# 2024-4T-MNT-1.net
KiCad netlist of a schematic drawn in EasyEDA Pro
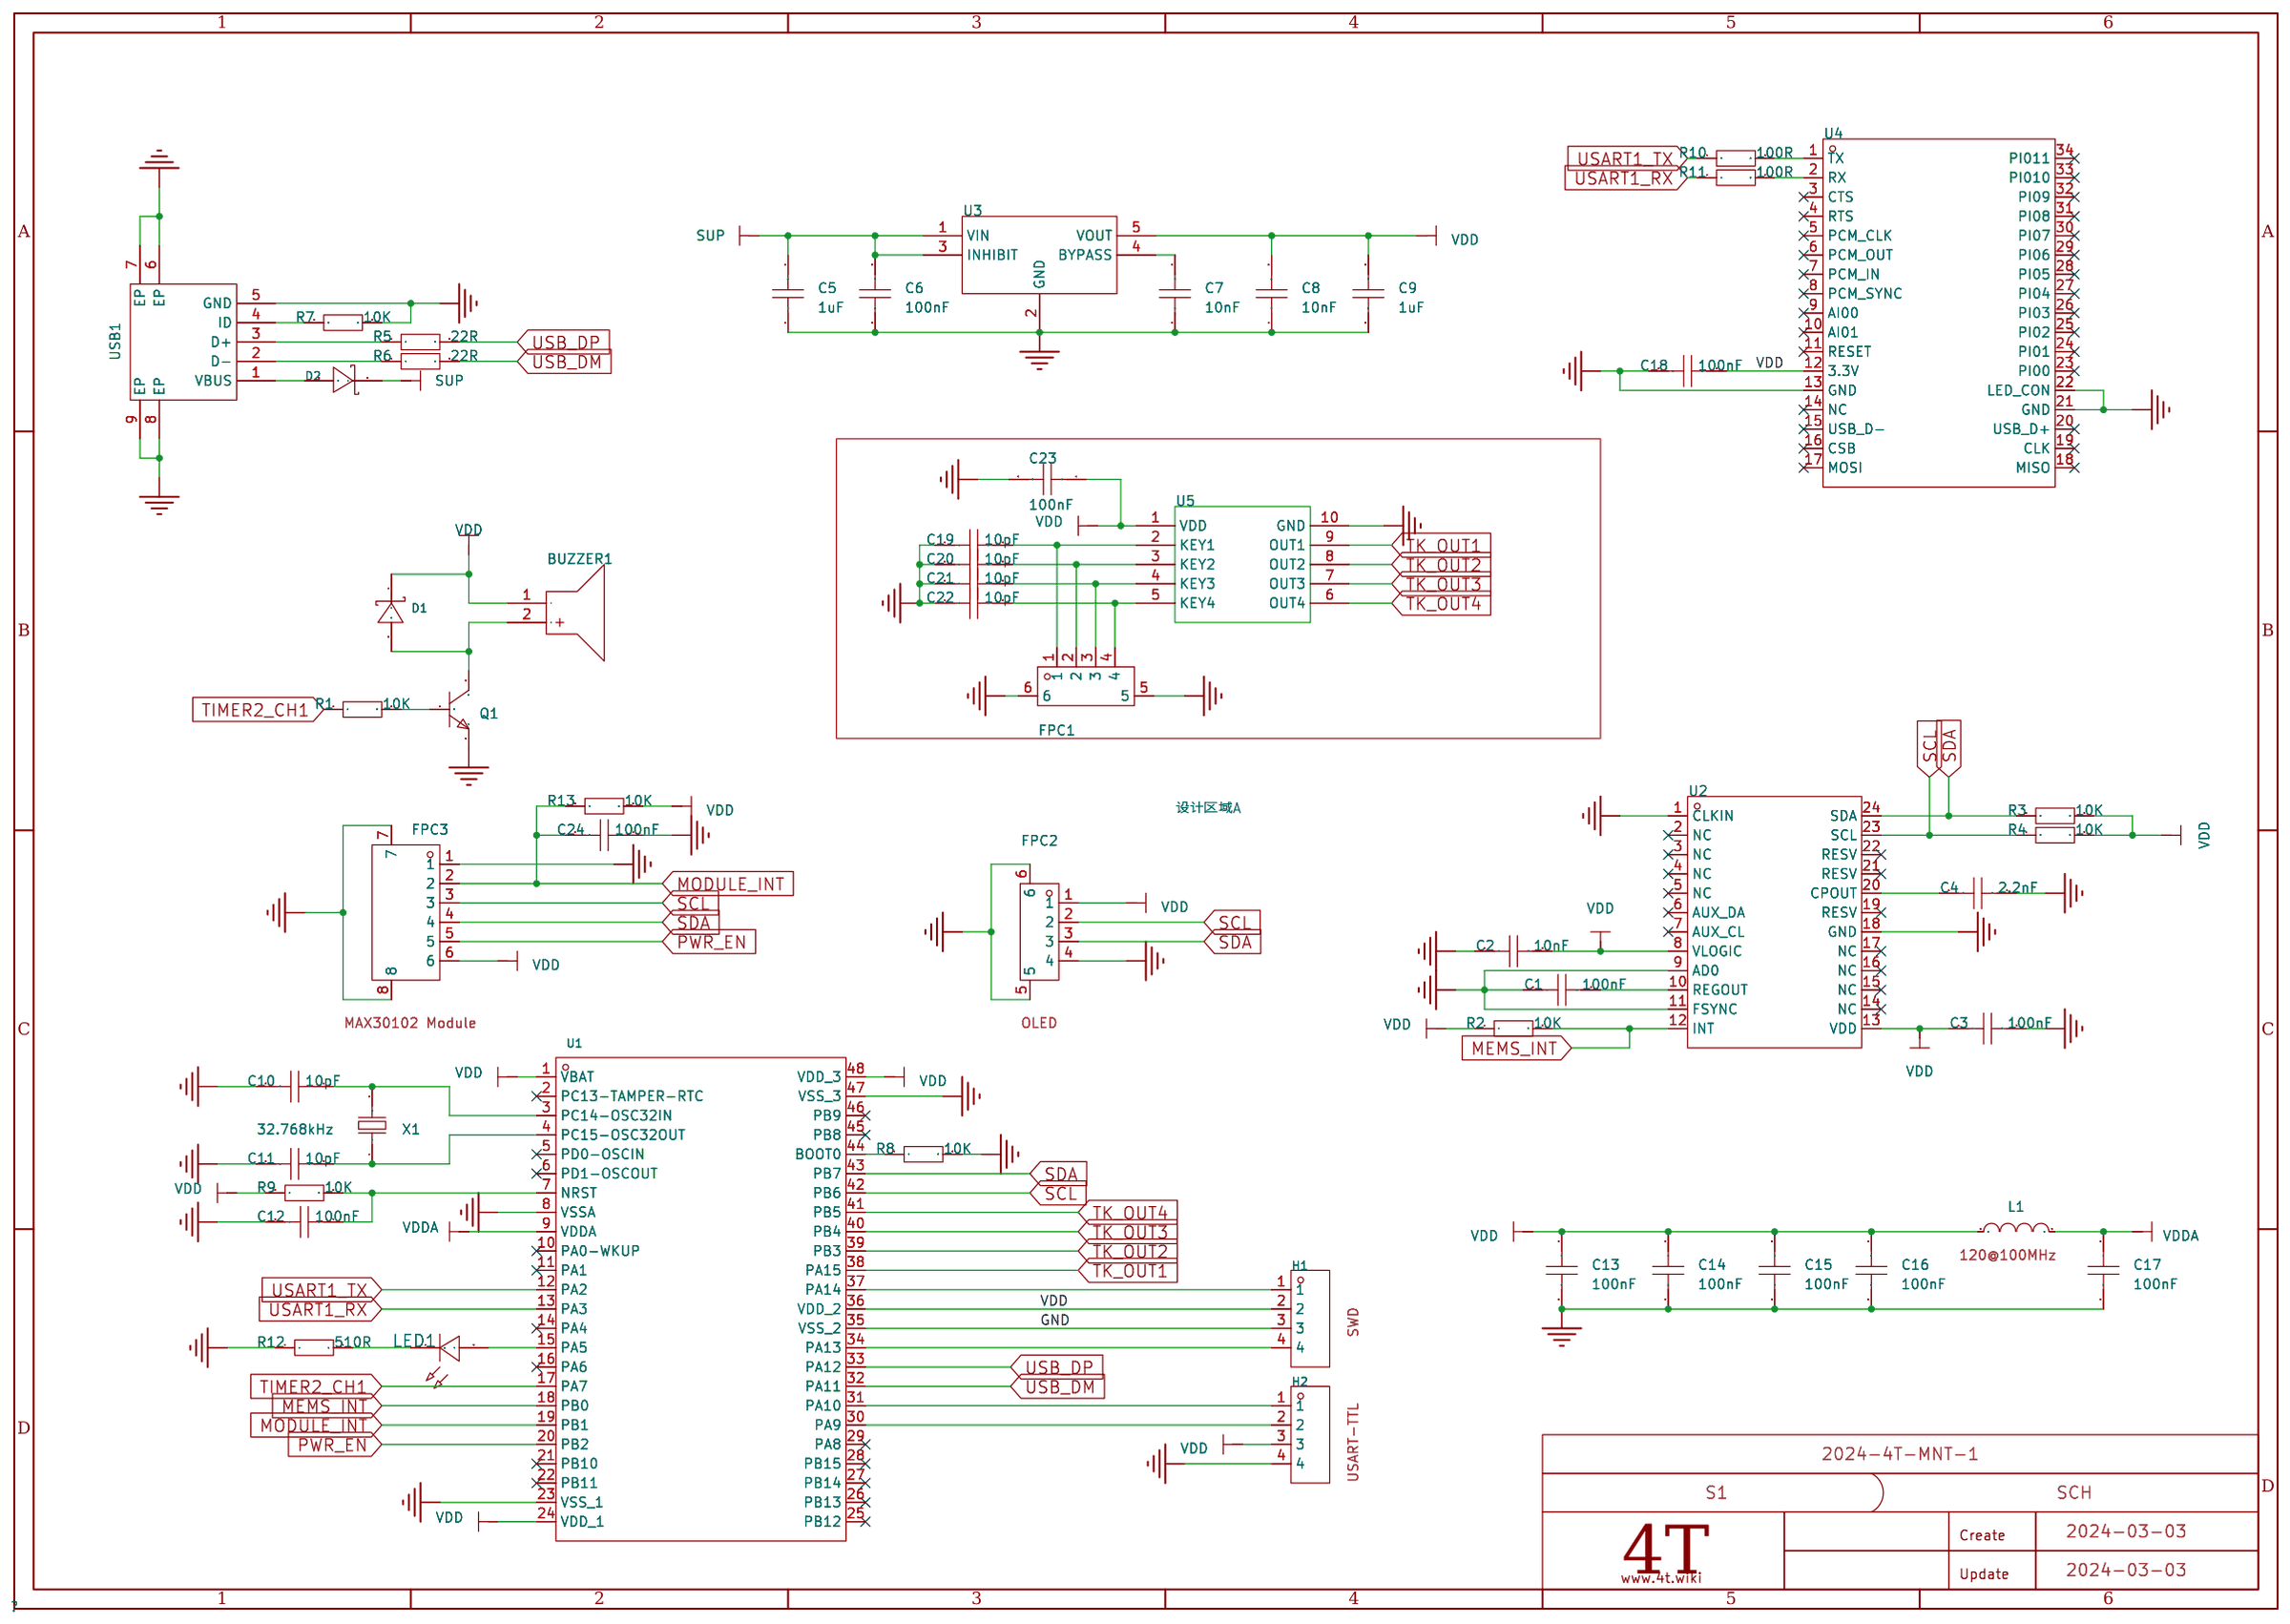
[diagram p0: schematic sheet]

(export (version "E")
  (design (tool "Eeschema 10.0.6"))
  (components
    (comp (ref "BUZZER1")
      (value "buzzer")
      (footprint "easyedapro:BUZ-TH_BD12.0-P6.00-D0.9-RD")
      (libsource (lib "easyedapro") (part "BUZZER"))
    )
    (comp (ref "C1")
      (value "100nF")
      (footprint "easyedapro:C0805")
      (libsource (lib "easyedapro") (part "CapAcitance"))
    )
    (comp (ref "C2")
      (value "10nF")
      (footprint "easyedapro:C0805")
      (libsource (lib "easyedapro") (part "CapAcitance"))
    )
    (comp (ref "C3")
      (value "100nF")
      (footprint "easyedapro:C0805")
      (libsource (lib "easyedapro") (part "CapAcitance"))
    )
    (comp (ref "C4")
      (value "2.2nF")
      (footprint "easyedapro:C0805")
      (libsource (lib "easyedapro") (part "CapAcitance"))
    )
    (comp (ref "C5")
      (value "1uF")
      (footprint "easyedapro:C0805")
      (libsource (lib "easyedapro") (part "CapAcitance"))
    )
    (comp (ref "C6")
      (value "100nF")
      (footprint "easyedapro:C0805")
      (libsource (lib "easyedapro") (part "CapAcitance"))
    )
    (comp (ref "C7")
      (value "10nF")
      (footprint "easyedapro:C0805")
      (libsource (lib "easyedapro") (part "CapAcitance"))
    )
    (comp (ref "C8")
      (value "10nF")
      (footprint "easyedapro:C0805")
      (libsource (lib "easyedapro") (part "CapAcitance"))
    )
    (comp (ref "C9")
      (value "1uF")
      (footprint "easyedapro:C0805")
      (libsource (lib "easyedapro") (part "CapAcitance"))
    )
    (comp (ref "C10")
      (value "10pF")
      (footprint "easyedapro:C0805")
      (libsource (lib "easyedapro") (part "CapAcitance"))
    )
    (comp (ref "C11")
      (value "10pF")
      (footprint "easyedapro:C0805")
      (libsource (lib "easyedapro") (part "CapAcitance"))
    )
    (comp (ref "C12")
      (value "100nF")
      (footprint "easyedapro:C0805")
      (libsource (lib "easyedapro") (part "CapAcitance"))
    )
    (comp (ref "C13")
      (value "100nF")
      (footprint "easyedapro:C0805")
      (libsource (lib "easyedapro") (part "CapAcitance"))
    )
    (comp (ref "C14")
      (value "100nF")
      (footprint "easyedapro:C0805")
      (libsource (lib "easyedapro") (part "CapAcitance"))
    )
    (comp (ref "C15")
      (value "100nF")
      (footprint "easyedapro:C0805")
      (libsource (lib "easyedapro") (part "CapAcitance"))
    )
    (comp (ref "C16")
      (value "100nF")
      (footprint "easyedapro:C0805")
      (libsource (lib "easyedapro") (part "CapAcitance"))
    )
    (comp (ref "C17")
      (value "100nF")
      (footprint "easyedapro:C0805")
      (libsource (lib "easyedapro") (part "CapAcitance"))
    )
    (comp (ref "C18")
      (value "100nF")
      (footprint "easyedapro:C0805")
      (libsource (lib "easyedapro") (part "CapAcitance"))
    )
    (comp (ref "C19")
      (value "10pF")
      (footprint "easyedapro:C0805")
      (libsource (lib "easyedapro") (part "CapAcitance"))
    )
    (comp (ref "C20")
      (value "10pF")
      (footprint "easyedapro:C0805")
      (libsource (lib "easyedapro") (part "CapAcitance"))
    )
    (comp (ref "C21")
      (value "10pF")
      (footprint "easyedapro:C0805")
      (libsource (lib "easyedapro") (part "CapAcitance"))
    )
    (comp (ref "C22")
      (value "10pF")
      (footprint "easyedapro:C0805")
      (libsource (lib "easyedapro") (part "CapAcitance"))
    )
    (comp (ref "C23")
      (value "100nF")
      (footprint "easyedapro:C0805")
      (libsource (lib "easyedapro") (part "CapAcitance"))
    )
    (comp (ref "C24")
      (value "100nF")
      (footprint "easyedapro:C0805")
      (libsource (lib "easyedapro") (part "CapAcitance"))
    )
    (comp (ref "D1")
      (value "SS14")
      (footprint "easyedapro:SMA_L4.2-W2.6-LS5.3-RD")
      (description "二极管配置:独立式;直流反向耐压(Vr):40V;平均整流电流(Io):1A;正向压降(Vf):550mV@1A;")
      (fields (field (name "Manufacturer") "MDD"))
      (libsource (lib "easyedapro") (part "SS14"))
    )
    (comp (ref "D2")
      (value "SS14")
      (footprint "easyedapro:SMA_L4.2-W2.6-LS5.3-RD")
      (description "二极管配置:独立式;直流反向耐压(Vr):40V;平均整流电流(Io):1A;正向压降(Vf):550mV@1A;")
      (fields (field (name "Manufacturer") "MDD"))
      (libsource (lib "easyedapro") (part "SS14"))
    )
    (comp (ref "FPC1")
      (value "FPC-4PIN-1.0MM-上接")
      (footprint "easyedapro:FPC-SMD_4P-P1.00_AFA07-S04ECC-00")
      (libsource (lib "easyedapro") (part "FPC-4PIN-1.0MM-上接"))
    )
    (comp (ref "FPC2")
      (value "FPC-4PIN-1.0MM-上接")
      (footprint "easyedapro:FPC-SMD_4P-P1.00_AFA07-S04ECC-00")
      (description "OLED")
      (libsource (lib "easyedapro") (part "FPC-4PIN-1.0MM-上接"))
    )
    (comp (ref "FPC3")
      (value "FPC6-0.5mm")
      (footprint "easyedapro:FPC-SMD_6P-L9.3-W4.1-P0.50")
      (description "MAX30102 Module")
      (libsource (lib "easyedapro") (part "FPC6-0.5MM"))
    )
    (comp (ref "H1")
      (value "~")
      (footprint "easyedapro:HDR-TH_4P-P2.54-V-F")
      (description "SWD")
      (libsource (lib "easyedapro") (part "2.54-1*4P母"))
    )
    (comp (ref "H2")
      (value "~")
      (footprint "easyedapro:HDR-TH_4P-P2.54-V-F")
      (description "USART-TTL")
      (libsource (lib "easyedapro") (part "2.54-1*4P母"))
    )
    (comp (ref "L1")
      (value "ACMS201209A6012A")
      (footprint "easyedapro:L0805")
      (description "120@100MHz")
      (fields (field (name "Manufacturer") "HYHONGYEX(宏业)"))
      (libsource (lib "easyedapro") (part "ACMS201209A6012A"))
    )
    (comp (ref "LED1")
      (value "~")
      (footprint "easyedapro:LED_0805")
      (libsource (lib "easyedapro") (part "LED_R"))
    )
    (comp (ref "Q1")
      (value "S8050")
      (footprint "easyedapro:SOT-23-3_L2.9-W1.3-P1.90-LS2.4-BR")
      (description "NPN 25V 500mA 120-400 SOT-23")
      (fields (field (name "Manufacturer") "Doeshare(德芯)"))
      (libsource (lib "easyedapro") (part "S8050_C2931719"))
    )
    (comp (ref "R1") (value "10K") (footprint "easyedapro:R0805") (libsource (lib "easyedapro") (part "电阻")))
    (comp (ref "R2") (value "10K") (footprint "easyedapro:R0805") (libsource (lib "easyedapro") (part "电阻")))
    (comp (ref "R3") (value "10K") (footprint "easyedapro:R0805") (libsource (lib "easyedapro") (part "电阻")))
    (comp (ref "R4") (value "10K") (footprint "easyedapro:R0805") (libsource (lib "easyedapro") (part "电阻")))
    (comp (ref "R5") (value "22R") (footprint "easyedapro:R0805") (libsource (lib "easyedapro") (part "电阻")))
    (comp (ref "R6") (value "22R") (footprint "easyedapro:R0805") (libsource (lib "easyedapro") (part "电阻")))
    (comp (ref "R7") (value "10K") (footprint "easyedapro:R0805") (libsource (lib "easyedapro") (part "电阻")))
    (comp (ref "R8") (value "10K") (footprint "easyedapro:R0805") (libsource (lib "easyedapro") (part "电阻")))
    (comp (ref "R9") (value "10K") (footprint "easyedapro:R0805") (libsource (lib "easyedapro") (part "电阻")))
    (comp (ref "R10")
      (value "100R")
      (footprint "easyedapro:R0805")
      (libsource (lib "easyedapro") (part "电阻"))
    )
    (comp (ref "R11")
      (value "100R")
      (footprint "easyedapro:R0805")
      (libsource (lib "easyedapro") (part "电阻"))
    )
    (comp (ref "R12")
      (value "510R")
      (footprint "easyedapro:R0805")
      (libsource (lib "easyedapro") (part "电阻"))
    )
    (comp (ref "R13") (value "10K") (footprint "easyedapro:R0805") (libsource (lib "easyedapro") (part "电阻")))
    (comp (ref "U1")
      (value "GD32F303CBT6")
      (footprint "easyedapro:LQFP-48_L7.0-W7.0-P0.50-LS9.0-BL")
      (libsource (lib "easyedapro") (part "GD32F303CBT6_C3013781"))
    )
    (comp (ref "U2")
      (value "MPU6050")
      (footprint "easyedapro:QFN-24_L4.0-W4.0-P0.50-BL")
      (libsource (lib "easyedapro") (part "MPU6050_C9900042518"))
    )
    (comp (ref "U3")
      (value "LD3985M33R")
      (footprint "easyedapro:SOT-23-5_L3.0-W1.7-P0.95-LS2.8-BR")
      (description "输出类型:固定;输出极性:正;最大输入电压:6V;输出电压:3.3V;输出电流:150mA;电源纹波抑制比(PSRR):60dB;")
      (fields (field (name "Manufacturer") "ST(意法半导体)"))
      (libsource (lib "easyedapro") (part "LD3985M33R"))
    )
    (comp (ref "U4")
      (value "HC-05")
      (footprint "easyedapro:BULETM-SMD_HC-05")
      (libsource (lib "easyedapro") (part "HC-05"))
    )
    (comp (ref "U5") (value "~") (libsource (lib "easyedapro") (part "CT4")))
    (comp (ref "USB1")
      (value "MicroUSB-5PIN")
      (footprint "easyedapro:USB-SMD_5P_MICROUSB-5PIN")
      (libsource (lib "easyedapro") (part "MICROUSB-5PIN"))
    )
    (comp (ref "X1")
      (value "32.768kHz")
      (footprint "easyedapro:FC-135R_L3.2-W1.5")
      (description "频率:32.768kHz;频率公差:±20ppm;负载电容:12.5pF;")
      (fields (field (name "Manufacturer Part") "Q13FC1350000400") (field (name "Manufacturer") "EPSON(爱普生)"))
      (libsource (lib "easyedapro") (part "Q13FC1350000400"))
    )
  )
  (nets
    (net (code "1") (name "GND") (class "Default")
      (node (ref "C1") (pin "1") (pinfunction "1_1") (pintype "input"))
      (node (ref "C10") (pin "2") (pinfunction "2_2") (pintype "input"))
      (node (ref "C11") (pin "2") (pinfunction "2_2") (pintype "input"))
      (node (ref "C12") (pin "2") (pinfunction "2_2") (pintype "input"))
      (node (ref "C13") (pin "2") (pinfunction "2_2") (pintype "input"))
      (node (ref "C14") (pin "2") (pinfunction "2_2") (pintype "input"))
      (node (ref "C15") (pin "2") (pinfunction "2_2") (pintype "input"))
      (node (ref "C16") (pin "2") (pinfunction "2_2") (pintype "input"))
      (node (ref "C17") (pin "2") (pinfunction "2_2") (pintype "input"))
      (node (ref "C18") (pin "1") (pinfunction "1_1") (pintype "input"))
      (node (ref "C19") (pin "1") (pinfunction "1_1") (pintype "input"))
      (node (ref "C2") (pin "1") (pinfunction "1_1") (pintype "input"))
      (node (ref "C20") (pin "1") (pinfunction "1_1") (pintype "input"))
      (node (ref "C21") (pin "1") (pinfunction "1_1") (pintype "input"))
      (node (ref "C22") (pin "1") (pinfunction "1_1") (pintype "input"))
      (node (ref "C23") (pin "2") (pinfunction "2_2") (pintype "input"))
      (node (ref "C24") (pin "1") (pinfunction "1_1") (pintype "input"))
      (node (ref "C3") (pin "2") (pinfunction "2_2") (pintype "input"))
      (node (ref "C4") (pin "2") (pinfunction "2_2") (pintype "input"))
      (node (ref "C5") (pin "1") (pinfunction "1_1") (pintype "input"))
      (node (ref "C6") (pin "1") (pinfunction "1_1") (pintype "input"))
      (node (ref "C7") (pin "1") (pinfunction "1_1") (pintype "input"))
      (node (ref "C8") (pin "1") (pinfunction "1_1") (pintype "input"))
      (node (ref "C9") (pin "1") (pinfunction "1_1") (pintype "input"))
      (node (ref "FPC1") (pin "5") (pinfunction "5_5") (pintype "input"))
      (node (ref "FPC1") (pin "6") (pinfunction "6_6") (pintype "input"))
      (node (ref "FPC2") (pin "4") (pinfunction "4_4") (pintype "input"))
      (node (ref "FPC2") (pin "5") (pinfunction "5_5") (pintype "input"))
      (node (ref "FPC2") (pin "6") (pinfunction "6_6") (pintype "input"))
      (node (ref "FPC3") (pin "1") (pinfunction "1_1") (pintype "input"))
      (node (ref "FPC3") (pin "7") (pinfunction "7_7") (pintype "input"))
      (node (ref "FPC3") (pin "8") (pinfunction "8_8") (pintype "input"))
      (node (ref "H1") (pin "3") (pinfunction "3_3") (pintype "input"))
      (node (ref "H2") (pin "4") (pinfunction "4_4") (pintype "input"))
      (node (ref "Q1") (pin "2") (pinfunction "E_2") (pintype "input"))
      (node (ref "R12") (pin "1") (pinfunction "1_1") (pintype "input"))
      (node (ref "R7") (pin "2") (pinfunction "2_2") (pintype "input"))
      (node (ref "R8") (pin "2") (pinfunction "2_2") (pintype "input"))
      (node (ref "U1") (pin "23") (pinfunction "VSS_1_23") (pintype "input"))
      (node (ref "U1") (pin "35") (pinfunction "VSS_2_35") (pintype "input"))
      (node (ref "U1") (pin "47") (pinfunction "VSS_3_47") (pintype "input"))
      (node (ref "U1") (pin "8") (pinfunction "VSSA_8") (pintype "input"))
      (node (ref "U2") (pin "1") (pinfunction "CLKIN_1") (pintype "input"))
      (node (ref "U2") (pin "11") (pinfunction "FSYNC_11") (pintype "input"))
      (node (ref "U2") (pin "18") (pinfunction "GND_18") (pintype "input"))
      (node (ref "U2") (pin "9") (pinfunction "AD0_9") (pintype "input"))
      (node (ref "U3") (pin "2") (pinfunction "GND_2") (pintype "unspecified"))
      (node (ref "U4") (pin "13") (pinfunction "GND_13") (pintype "input"))
      (node (ref "U4") (pin "21") (pinfunction "GND_21") (pintype "input"))
      (node (ref "U4") (pin "22") (pinfunction "LED_CON_22") (pintype "input"))
      (node (ref "U5") (pin "10") (pinfunction "GND_10") (pintype "input"))
      (node (ref "USB1") (pin "5") (pinfunction "GND_5") (pintype "input"))
      (node (ref "USB1") (pin "6") (pinfunction "EP_6") (pintype "input"))
      (node (ref "USB1") (pin "7") (pinfunction "EP_7") (pintype "input"))
      (node (ref "USB1") (pin "8") (pinfunction "EP_8") (pintype "input"))
      (node (ref "USB1") (pin "9") (pinfunction "EP_9") (pintype "input"))
    )
    (net (code "2") (name "MEMS_INT") (class "Default")
      (node (ref "R2") (pin "2") (pinfunction "2_2") (pintype "input"))
      (node (ref "U1") (pin "18") (pinfunction "PB0_18") (pintype "input"))
      (node (ref "U2") (pin "12") (pinfunction "INT_12") (pintype "input"))
    )
    (net (code "3") (name "MODULE_INT") (class "Default")
      (node (ref "C24") (pin "2") (pinfunction "2_2") (pintype "input"))
      (node (ref "FPC3") (pin "2") (pinfunction "2_2") (pintype "input"))
      (node (ref "R13") (pin "1") (pinfunction "1_1") (pintype "input"))
      (node (ref "U1") (pin "19") (pinfunction "PB1_19") (pintype "input"))
    )
    (net (code "4") (name "Net-(BUZZER1-+)") (class "Default")
      (node (ref "BUZZER1") (pin "2") (pinfunction "+_2") (pintype "input"))
      (node (ref "D1") (pin "2") (pinfunction "A_2") (pintype "input"))
      (node (ref "Q1") (pin "3") (pinfunction "C_3") (pintype "input"))
    )
    (net (code "5") (name "Net-(D2-A)") (class "Default")
      (node (ref "D2") (pin "2") (pinfunction "A_2") (pintype "input"))
      (node (ref "USB1") (pin "1") (pinfunction "VBUS_1") (pintype "input"))
    )
    (net (code "6") (name "Net-(LED1-A)") (class "Default")
      (node (ref "LED1") (pin "2") (pinfunction "A_2") (pintype "input"))
      (node (ref "U1") (pin "15") (pinfunction "PA5_15") (pintype "input"))
    )
    (net (code "7") (name "Net-(LED1-C)") (class "Default")
      (node (ref "LED1") (pin "1") (pinfunction "C_1") (pintype "input"))
      (node (ref "R12") (pin "2") (pinfunction "2_2") (pintype "input"))
    )
    (net (code "8") (name "Net-(Q1-B)") (class "Default")
      (node (ref "Q1") (pin "1") (pinfunction "B_1") (pintype "input"))
      (node (ref "R1") (pin "2") (pinfunction "2_2") (pintype "input"))
    )
    (net (code "9") (name "Net-(U1-BOOT0)") (class "Default")
      (node (ref "R8") (pin "1") (pinfunction "1_1") (pintype "input"))
      (node (ref "U1") (pin "44") (pinfunction "BOOT0_44") (pintype "input"))
    )
    (net (code "10") (name "Net-(U1-NRST)") (class "Default")
      (node (ref "C12") (pin "1") (pinfunction "1_1") (pintype "input"))
      (node (ref "R9") (pin "2") (pinfunction "2_2") (pintype "input"))
      (node (ref "U1") (pin "7") (pinfunction "NRST_7") (pintype "input"))
    )
    (net (code "11") (name "Net-(U1-PA9)") (class "Default")
      (node (ref "H2") (pin "2") (pinfunction "2_2") (pintype "input"))
      (node (ref "U1") (pin "30") (pinfunction "PA9_30") (pintype "input"))
    )
    (net (code "12") (name "Net-(U1-PA10)") (class "Default")
      (node (ref "H2") (pin "1") (pinfunction "1_1") (pintype "input"))
      (node (ref "U1") (pin "31") (pinfunction "PA10_31") (pintype "input"))
    )
    (net (code "13") (name "Net-(U1-PA13)") (class "Default")
      (node (ref "H1") (pin "4") (pinfunction "4_4") (pintype "input"))
      (node (ref "U1") (pin "34") (pinfunction "PA13_34") (pintype "input"))
    )
    (net (code "14") (name "Net-(U1-PA14)") (class "Default")
      (node (ref "H1") (pin "1") (pinfunction "1_1") (pintype "input"))
      (node (ref "U1") (pin "37") (pinfunction "PA14_37") (pintype "input"))
    )
    (net (code "15") (name "Net-(U1-PC14-OSC32IN)") (class "Default")
      (node (ref "C10") (pin "1") (pinfunction "1_1") (pintype "input"))
      (node (ref "U1") (pin "3") (pinfunction "PC14-OSC32IN_3") (pintype "input"))
      (node (ref "X1") (pin "2") (pinfunction "2_2") (pintype "input"))
    )
    (net (code "16") (name "Net-(U1-PC15-OSC32OUT)") (class "Default")
      (node (ref "C11") (pin "1") (pinfunction "1_1") (pintype "input"))
      (node (ref "U1") (pin "4") (pinfunction "PC15-OSC32OUT_4") (pintype "input"))
      (node (ref "X1") (pin "1") (pinfunction "1_1") (pintype "input"))
    )
    (net (code "17") (name "Net-(U2-CPOUT)") (class "Default")
      (node (ref "C4") (pin "1") (pinfunction "1_1") (pintype "input"))
      (node (ref "U2") (pin "20") (pinfunction "CPOUT_20") (pintype "input"))
    )
    (net (code "18") (name "Net-(U2-REGOUT)") (class "Default")
      (node (ref "C1") (pin "2") (pinfunction "2_2") (pintype "input"))
      (node (ref "U2") (pin "10") (pinfunction "REGOUT_10") (pintype "input"))
    )
    (net (code "19") (name "Net-(U3-BYPASS)") (class "Default")
      (node (ref "C7") (pin "2") (pinfunction "2_2") (pintype "input"))
      (node (ref "U3") (pin "4") (pinfunction "BYPASS_4") (pintype "unspecified"))
    )
    (net (code "20") (name "Net-(U4-RX)") (class "Default")
      (node (ref "R11") (pin "2") (pinfunction "2_2") (pintype "input"))
      (node (ref "U4") (pin "2") (pinfunction "RX_2") (pintype "input"))
    )
    (net (code "21") (name "Net-(U4-TX)") (class "Default")
      (node (ref "R10") (pin "2") (pinfunction "2_2") (pintype "input"))
      (node (ref "U4") (pin "1") (pinfunction "TX_1") (pintype "input"))
    )
    (net (code "22") (name "Net-(U5-KEY1)") (class "Default")
      (node (ref "C19") (pin "2") (pinfunction "2_2") (pintype "input"))
      (node (ref "FPC1") (pin "1") (pinfunction "1_1") (pintype "input"))
      (node (ref "U5") (pin "2") (pinfunction "KEY1_2") (pintype "input"))
    )
    (net (code "23") (name "Net-(U5-KEY2)") (class "Default")
      (node (ref "C20") (pin "2") (pinfunction "2_2") (pintype "input"))
      (node (ref "FPC1") (pin "2") (pinfunction "2_2") (pintype "input"))
      (node (ref "U5") (pin "3") (pinfunction "KEY2_3") (pintype "input"))
    )
    (net (code "24") (name "Net-(U5-KEY3)") (class "Default")
      (node (ref "C21") (pin "2") (pinfunction "2_2") (pintype "input"))
      (node (ref "FPC1") (pin "3") (pinfunction "3_3") (pintype "input"))
      (node (ref "U5") (pin "4") (pinfunction "KEY3_4") (pintype "input"))
    )
    (net (code "25") (name "Net-(U5-KEY4)") (class "Default")
      (node (ref "C22") (pin "2") (pinfunction "2_2") (pintype "input"))
      (node (ref "FPC1") (pin "4") (pinfunction "4_4") (pintype "input"))
      (node (ref "U5") (pin "5") (pinfunction "KEY4_5") (pintype "input"))
    )
    (net (code "26") (name "Net-(USB1-D+)") (class "Default")
      (node (ref "R5") (pin "1") (pinfunction "1_1") (pintype "input"))
      (node (ref "USB1") (pin "3") (pinfunction "D+_3") (pintype "input"))
    )
    (net (code "27") (name "Net-(USB1-D-)") (class "Default")
      (node (ref "R6") (pin "1") (pinfunction "1_1") (pintype "input"))
      (node (ref "USB1") (pin "2") (pinfunction "D-_2") (pintype "input"))
    )
    (net (code "28") (name "Net-(USB1-ID)") (class "Default")
      (node (ref "R7") (pin "1") (pinfunction "1_1") (pintype "input"))
      (node (ref "USB1") (pin "4") (pinfunction "ID_4") (pintype "input"))
    )
    (net (code "29") (name "PWR_EN") (class "Default")
      (node (ref "FPC3") (pin "5") (pinfunction "5_5") (pintype "input"))
      (node (ref "U1") (pin "20") (pinfunction "PB2_20") (pintype "input"))
    )
    (net (code "30") (name "SCL") (class "Default")
      (node (ref "FPC2") (pin "2") (pinfunction "2_2") (pintype "input"))
      (node (ref "FPC3") (pin "3") (pinfunction "3_3") (pintype "input"))
      (node (ref "R4") (pin "1") (pinfunction "1_1") (pintype "input"))
      (node (ref "U1") (pin "42") (pinfunction "PB6_42") (pintype "input"))
      (node (ref "U2") (pin "23") (pinfunction "SCL_23") (pintype "input"))
    )
    (net (code "31") (name "SDA") (class "Default")
      (node (ref "FPC2") (pin "3") (pinfunction "3_3") (pintype "input"))
      (node (ref "FPC3") (pin "4") (pinfunction "4_4") (pintype "input"))
      (node (ref "R3") (pin "1") (pinfunction "1_1") (pintype "input"))
      (node (ref "U1") (pin "43") (pinfunction "PB7_43") (pintype "input"))
      (node (ref "U2") (pin "24") (pinfunction "SDA_24") (pintype "input"))
    )
    (net (code "32") (name "SUP") (class "Default")
      (node (ref "C5") (pin "2") (pinfunction "2_2") (pintype "input"))
      (node (ref "C6") (pin "2") (pinfunction "2_2") (pintype "input"))
      (node (ref "D2") (pin "1") (pinfunction "K_1") (pintype "input"))
      (node (ref "U3") (pin "1") (pinfunction "VIN_1") (pintype "unspecified"))
      (node (ref "U3") (pin "3") (pinfunction "INHIBIT_3") (pintype "unspecified"))
    )
    (net (code "33") (name "TIMER2_CH1") (class "Default")
      (node (ref "R1") (pin "1") (pinfunction "1_1") (pintype "input"))
      (node (ref "U1") (pin "17") (pinfunction "PA7_17") (pintype "input"))
    )
    (net (code "34") (name "TK_OUT1") (class "Default")
      (node (ref "U1") (pin "38") (pinfunction "PA15_38") (pintype "input"))
      (node (ref "U5") (pin "9") (pinfunction "OUT1_9") (pintype "input"))
    )
    (net (code "35") (name "TK_OUT2") (class "Default")
      (node (ref "U1") (pin "39") (pinfunction "PB3_39") (pintype "input"))
      (node (ref "U5") (pin "8") (pinfunction "OUT2_8") (pintype "input"))
    )
    (net (code "36") (name "TK_OUT3") (class "Default")
      (node (ref "U1") (pin "40") (pinfunction "PB4_40") (pintype "input"))
      (node (ref "U5") (pin "7") (pinfunction "OUT3_7") (pintype "input"))
    )
    (net (code "37") (name "TK_OUT4") (class "Default")
      (node (ref "U1") (pin "41") (pinfunction "PB5_41") (pintype "input"))
      (node (ref "U5") (pin "6") (pinfunction "OUT4_6") (pintype "input"))
    )
    (net (code "38") (name "USART1_RX") (class "Default")
      (node (ref "R11") (pin "1") (pinfunction "1_1") (pintype "input"))
      (node (ref "U1") (pin "13") (pinfunction "PA3_13") (pintype "input"))
    )
    (net (code "39") (name "USART1_TX") (class "Default")
      (node (ref "R10") (pin "1") (pinfunction "1_1") (pintype "input"))
      (node (ref "U1") (pin "12") (pinfunction "PA2_12") (pintype "input"))
    )
    (net (code "40") (name "USB_DM") (class "Default")
      (node (ref "R6") (pin "2") (pinfunction "2_2") (pintype "input"))
      (node (ref "U1") (pin "32") (pinfunction "PA11_32") (pintype "input"))
    )
    (net (code "41") (name "USB_DP") (class "Default")
      (node (ref "R5") (pin "2") (pinfunction "2_2") (pintype "input"))
      (node (ref "U1") (pin "33") (pinfunction "PA12_33") (pintype "input"))
    )
    (net (code "42") (name "VDD") (class "Default")
      (node (ref "BUZZER1") (pin "1") (pinfunction "-_1") (pintype "input"))
      (node (ref "C13") (pin "1") (pinfunction "1_1") (pintype "input"))
      (node (ref "C14") (pin "1") (pinfunction "1_1") (pintype "input"))
      (node (ref "C15") (pin "1") (pinfunction "1_1") (pintype "input"))
      (node (ref "C16") (pin "1") (pinfunction "1_1") (pintype "input"))
      (node (ref "C18") (pin "2") (pinfunction "2_2") (pintype "input"))
      (node (ref "C2") (pin "2") (pinfunction "2_2") (pintype "input"))
      (node (ref "C23") (pin "1") (pinfunction "1_1") (pintype "input"))
      (node (ref "C3") (pin "1") (pinfunction "1_1") (pintype "input"))
      (node (ref "C8") (pin "2") (pinfunction "2_2") (pintype "input"))
      (node (ref "C9") (pin "2") (pinfunction "2_2") (pintype "input"))
      (node (ref "D1") (pin "1") (pinfunction "K_1") (pintype "input"))
      (node (ref "FPC2") (pin "1") (pinfunction "1_1") (pintype "input"))
      (node (ref "FPC3") (pin "6") (pinfunction "6_6") (pintype "input"))
      (node (ref "H1") (pin "2") (pinfunction "2_2") (pintype "input"))
      (node (ref "H2") (pin "3") (pinfunction "3_3") (pintype "input"))
      (node (ref "L1") (pin "1") (pinfunction "1_1") (pintype "input"))
      (node (ref "R13") (pin "2") (pinfunction "2_2") (pintype "input"))
      (node (ref "R2") (pin "1") (pinfunction "1_1") (pintype "input"))
      (node (ref "R3") (pin "2") (pinfunction "2_2") (pintype "input"))
      (node (ref "R4") (pin "2") (pinfunction "2_2") (pintype "input"))
      (node (ref "R9") (pin "1") (pinfunction "1_1") (pintype "input"))
      (node (ref "U1") (pin "1") (pinfunction "VBAT_1") (pintype "input"))
      (node (ref "U1") (pin "24") (pinfunction "VDD_1_24") (pintype "input"))
      (node (ref "U1") (pin "36") (pinfunction "VDD_2_36") (pintype "input"))
      (node (ref "U1") (pin "48") (pinfunction "VDD_3_48") (pintype "input"))
      (node (ref "U2") (pin "13") (pinfunction "VDD_13") (pintype "input"))
      (node (ref "U2") (pin "8") (pinfunction "VLOGIC_8") (pintype "input"))
      (node (ref "U3") (pin "5") (pinfunction "VOUT_5") (pintype "unspecified"))
      (node (ref "U4") (pin "12") (pinfunction "3.3V_12") (pintype "input"))
      (node (ref "U5") (pin "1") (pinfunction "VDD_1") (pintype "input"))
    )
    (net (code "43") (name "VDDA") (class "Default")
      (node (ref "C17") (pin "1") (pinfunction "1_1") (pintype "input"))
      (node (ref "L1") (pin "2") (pinfunction "2_2") (pintype "input"))
      (node (ref "U1") (pin "9") (pinfunction "VDDA_9") (pintype "input"))
    )
    (net (code "44") (name "unconnected-(U1-PA0-WKUP-Pad10)") (class "Default")
      (node (ref "U1") (pin "10") (pinfunction "PA0-WKUP_10") (pintype "input+no_connect"))
    )
    (net (code "45") (name "unconnected-(U1-PA1-Pad11)") (class "Default")
      (node (ref "U1") (pin "11") (pinfunction "PA1_11") (pintype "input+no_connect"))
    )
    (net (code "46") (name "unconnected-(U1-PA4-Pad14)") (class "Default")
      (node (ref "U1") (pin "14") (pinfunction "PA4_14") (pintype "input+no_connect"))
    )
    (net (code "47") (name "unconnected-(U1-PA6-Pad16)") (class "Default")
      (node (ref "U1") (pin "16") (pinfunction "PA6_16") (pintype "input+no_connect"))
    )
    (net (code "48") (name "unconnected-(U1-PA8-Pad29)") (class "Default")
      (node (ref "U1") (pin "29") (pinfunction "PA8_29") (pintype "input+no_connect"))
    )
    (net (code "49") (name "unconnected-(U1-PB8-Pad45)") (class "Default")
      (node (ref "U1") (pin "45") (pinfunction "PB8_45") (pintype "input+no_connect"))
    )
    (net (code "50") (name "unconnected-(U1-PB9-Pad46)") (class "Default")
      (node (ref "U1") (pin "46") (pinfunction "PB9_46") (pintype "input+no_connect"))
    )
    (net (code "51") (name "unconnected-(U1-PB10-Pad21)") (class "Default")
      (node (ref "U1") (pin "21") (pinfunction "PB10_21") (pintype "input+no_connect"))
    )
    (net (code "52") (name "unconnected-(U1-PB11-Pad22)") (class "Default")
      (node (ref "U1") (pin "22") (pinfunction "PB11_22") (pintype "input+no_connect"))
    )
    (net (code "53") (name "unconnected-(U1-PB12-Pad25)") (class "Default")
      (node (ref "U1") (pin "25") (pinfunction "PB12_25") (pintype "input+no_connect"))
    )
    (net (code "54") (name "unconnected-(U1-PB13-Pad26)") (class "Default")
      (node (ref "U1") (pin "26") (pinfunction "PB13_26") (pintype "input+no_connect"))
    )
    (net (code "55") (name "unconnected-(U1-PB14-Pad27)") (class "Default")
      (node (ref "U1") (pin "27") (pinfunction "PB14_27") (pintype "input+no_connect"))
    )
    (net (code "56") (name "unconnected-(U1-PB15-Pad28)") (class "Default")
      (node (ref "U1") (pin "28") (pinfunction "PB15_28") (pintype "input+no_connect"))
    )
    (net (code "57") (name "unconnected-(U1-PC13-TAMPER-RTC-Pad2)") (class "Default")
      (node (ref "U1") (pin "2") (pinfunction "PC13-TAMPER-RTC_2") (pintype "input+no_connect"))
    )
    (net (code "58") (name "unconnected-(U1-PD0-OSCIN-Pad5)") (class "Default")
      (node (ref "U1") (pin "5") (pinfunction "PD0-OSCIN_5") (pintype "input+no_connect"))
    )
    (net (code "59") (name "unconnected-(U1-PD1-OSCOUT-Pad6)") (class "Default")
      (node (ref "U1") (pin "6") (pinfunction "PD1-OSCOUT_6") (pintype "input+no_connect"))
    )
    (net (code "60") (name "unconnected-(U2-AUX_CL-Pad7)") (class "Default")
      (node (ref "U2") (pin "7") (pinfunction "AUX_CL_7") (pintype "input+no_connect"))
    )
    (net (code "61") (name "unconnected-(U2-AUX_DA-Pad6)") (class "Default")
      (node (ref "U2") (pin "6") (pinfunction "AUX_DA_6") (pintype "input+no_connect"))
    )
    (net (code "62") (name "unconnected-(U2-NC-Pad2)") (class "Default")
      (node (ref "U2") (pin "2") (pinfunction "NC_2") (pintype "input+no_connect"))
    )
    (net (code "63") (name "unconnected-(U2-NC-Pad3)") (class "Default")
      (node (ref "U2") (pin "3") (pinfunction "NC_3") (pintype "input+no_connect"))
    )
    (net (code "64") (name "unconnected-(U2-NC-Pad4)") (class "Default")
      (node (ref "U2") (pin "4") (pinfunction "NC_4") (pintype "input+no_connect"))
    )
    (net (code "65") (name "unconnected-(U2-NC-Pad5)") (class "Default")
      (node (ref "U2") (pin "5") (pinfunction "NC_5") (pintype "input+no_connect"))
    )
    (net (code "66") (name "unconnected-(U2-NC-Pad14)") (class "Default")
      (node (ref "U2") (pin "14") (pinfunction "NC_14") (pintype "input+no_connect"))
    )
    (net (code "67") (name "unconnected-(U2-NC-Pad15)") (class "Default")
      (node (ref "U2") (pin "15") (pinfunction "NC_15") (pintype "input+no_connect"))
    )
    (net (code "68") (name "unconnected-(U2-NC-Pad16)") (class "Default")
      (node (ref "U2") (pin "16") (pinfunction "NC_16") (pintype "input+no_connect"))
    )
    (net (code "69") (name "unconnected-(U2-NC-Pad17)") (class "Default")
      (node (ref "U2") (pin "17") (pinfunction "NC_17") (pintype "input+no_connect"))
    )
    (net (code "70") (name "unconnected-(U2-RESV-Pad19)") (class "Default")
      (node (ref "U2") (pin "19") (pinfunction "RESV_19") (pintype "input+no_connect"))
    )
    (net (code "71") (name "unconnected-(U2-RESV-Pad21)") (class "Default")
      (node (ref "U2") (pin "21") (pinfunction "RESV_21") (pintype "input+no_connect"))
    )
    (net (code "72") (name "unconnected-(U2-RESV-Pad22)") (class "Default")
      (node (ref "U2") (pin "22") (pinfunction "RESV_22") (pintype "input+no_connect"))
    )
    (net (code "73") (name "unconnected-(U4-AI00-Pad9)") (class "Default")
      (node (ref "U4") (pin "9") (pinfunction "AI00_9") (pintype "input+no_connect"))
    )
    (net (code "74") (name "unconnected-(U4-AI01-Pad10)") (class "Default")
      (node (ref "U4") (pin "10") (pinfunction "AI01_10") (pintype "input+no_connect"))
    )
    (net (code "75") (name "unconnected-(U4-CLK-Pad19)") (class "Default")
      (node (ref "U4") (pin "19") (pinfunction "CLK_19") (pintype "input+no_connect"))
    )
    (net (code "76") (name "unconnected-(U4-CSB-Pad16)") (class "Default")
      (node (ref "U4") (pin "16") (pinfunction "CSB_16") (pintype "input+no_connect"))
    )
    (net (code "77") (name "unconnected-(U4-CTS-Pad3)") (class "Default")
      (node (ref "U4") (pin "3") (pinfunction "CTS_3") (pintype "input+no_connect"))
    )
    (net (code "78") (name "unconnected-(U4-MISO-Pad18)") (class "Default")
      (node (ref "U4") (pin "18") (pinfunction "MISO_18") (pintype "input+no_connect"))
    )
    (net (code "79") (name "unconnected-(U4-MOSI-Pad17)") (class "Default")
      (node (ref "U4") (pin "17") (pinfunction "MOSI_17") (pintype "input+no_connect"))
    )
    (net (code "80") (name "unconnected-(U4-NC-Pad14)") (class "Default")
      (node (ref "U4") (pin "14") (pinfunction "NC_14") (pintype "input+no_connect"))
    )
    (net (code "81") (name "unconnected-(U4-PCM_CLK-Pad5)") (class "Default")
      (node (ref "U4") (pin "5") (pinfunction "PCM_CLK_5") (pintype "input+no_connect"))
    )
    (net (code "82") (name "unconnected-(U4-PCM_IN-Pad7)") (class "Default")
      (node (ref "U4") (pin "7") (pinfunction "PCM_IN_7") (pintype "input+no_connect"))
    )
    (net (code "83") (name "unconnected-(U4-PCM_OUT-Pad6)") (class "Default")
      (node (ref "U4") (pin "6") (pinfunction "PCM_OUT_6") (pintype "input+no_connect"))
    )
    (net (code "84") (name "unconnected-(U4-PCM_SYNC-Pad8)") (class "Default")
      (node (ref "U4") (pin "8") (pinfunction "PCM_SYNC_8") (pintype "input+no_connect"))
    )
    (net (code "85") (name "unconnected-(U4-PI00-Pad23)") (class "Default")
      (node (ref "U4") (pin "23") (pinfunction "PI00_23") (pintype "input+no_connect"))
    )
    (net (code "86") (name "unconnected-(U4-PI01-Pad24)") (class "Default")
      (node (ref "U4") (pin "24") (pinfunction "PI01_24") (pintype "input+no_connect"))
    )
    (net (code "87") (name "unconnected-(U4-PI02-Pad25)") (class "Default")
      (node (ref "U4") (pin "25") (pinfunction "PI02_25") (pintype "input+no_connect"))
    )
    (net (code "88") (name "unconnected-(U4-PI03-Pad26)") (class "Default")
      (node (ref "U4") (pin "26") (pinfunction "PI03_26") (pintype "input+no_connect"))
    )
    (net (code "89") (name "unconnected-(U4-PI04-Pad27)") (class "Default")
      (node (ref "U4") (pin "27") (pinfunction "PI04_27") (pintype "input+no_connect"))
    )
    (net (code "90") (name "unconnected-(U4-PI05-Pad28)") (class "Default")
      (node (ref "U4") (pin "28") (pinfunction "PI05_28") (pintype "input+no_connect"))
    )
    (net (code "91") (name "unconnected-(U4-PI06-Pad29)") (class "Default")
      (node (ref "U4") (pin "29") (pinfunction "PI06_29") (pintype "input+no_connect"))
    )
    (net (code "92") (name "unconnected-(U4-PI07-Pad30)") (class "Default")
      (node (ref "U4") (pin "30") (pinfunction "PI07_30") (pintype "input+no_connect"))
    )
    (net (code "93") (name "unconnected-(U4-PI08-Pad31)") (class "Default")
      (node (ref "U4") (pin "31") (pinfunction "PI08_31") (pintype "input+no_connect"))
    )
    (net (code "94") (name "unconnected-(U4-PI09-Pad32)") (class "Default")
      (node (ref "U4") (pin "32") (pinfunction "PI09_32") (pintype "input+no_connect"))
    )
    (net (code "95") (name "unconnected-(U4-PI010-Pad33)") (class "Default")
      (node (ref "U4") (pin "33") (pinfunction "PI010_33") (pintype "input+no_connect"))
    )
    (net (code "96") (name "unconnected-(U4-PI011-Pad34)") (class "Default")
      (node (ref "U4") (pin "34") (pinfunction "PI011_34") (pintype "input+no_connect"))
    )
    (net (code "97") (name "unconnected-(U4-RESET-Pad11)") (class "Default")
      (node (ref "U4") (pin "11") (pinfunction "RESET_11") (pintype "input+no_connect"))
    )
    (net (code "98") (name "unconnected-(U4-RTS-Pad4)") (class "Default")
      (node (ref "U4") (pin "4") (pinfunction "RTS_4") (pintype "input+no_connect"))
    )
    (net (code "99") (name "unconnected-(U4-USB_D+-Pad20)") (class "Default")
      (node (ref "U4") (pin "20") (pinfunction "USB_D+_20") (pintype "input+no_connect"))
    )
    (net (code "100") (name "unconnected-(U4-USB_D--Pad15)") (class "Default")
      (node (ref "U4") (pin "15") (pinfunction "USB_D-_15") (pintype "input+no_connect"))
    )
  )
)
